# VESC_POWER_SCH.net
KiCad netlist of a schematic drawn in Altium Designer
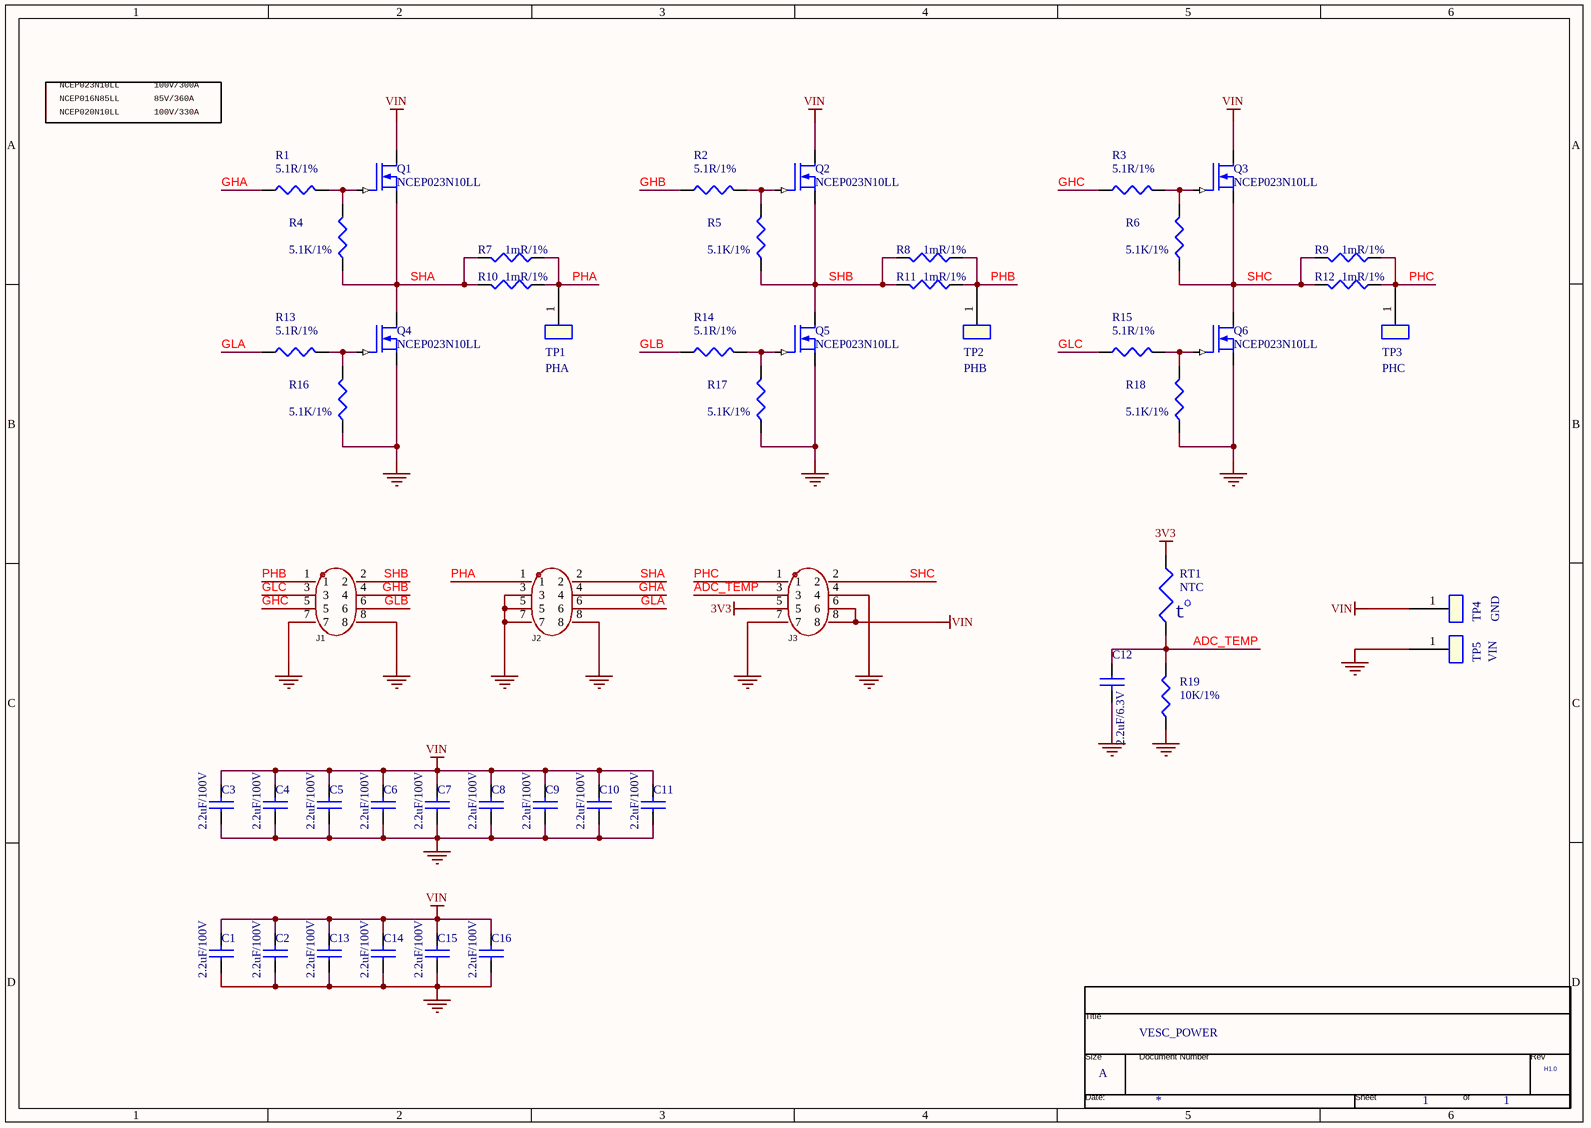
[diagram p0: VESC_POWER_SCH.SchDoc]

(export (version "E")
  (design (tool "Eeschema 10.0.6"))
  (components
    (comp (ref "*")
      (value "TitleBlock0")
      (fields
        (field (name "REVCODE") "H1.0")
        (field (name "TITLE") "VESC_POWER")
        (field (name "PAGE SIZE") "A")
        (field (name "PAGE NUMBER") "1")
        (field (name "PAGE COUNT") "1")
      )
      (libsource (lib "*") (part "TitleBlock0"))
    )
    (comp (ref "C1") (value "2.2uF/100V") (footprint "CAPC3225X230N") (libsource (lib "*") (part "CAP NP")))
    (comp (ref "C2") (value "2.2uF/100V") (footprint "CAPC3225X230N") (libsource (lib "*") (part "CAP NP")))
    (comp (ref "C3") (value "2.2uF/100V") (footprint "CAPC3225X230N") (libsource (lib "*") (part "CAP NP")))
    (comp (ref "C4") (value "2.2uF/100V") (footprint "CAPC3225X230N") (libsource (lib "*") (part "CAP NP")))
    (comp (ref "C5") (value "2.2uF/100V") (footprint "CAPC3225X230N") (libsource (lib "*") (part "CAP NP")))
    (comp (ref "C6") (value "2.2uF/100V") (footprint "CAPC3225X230N") (libsource (lib "*") (part "CAP NP")))
    (comp (ref "C7") (value "2.2uF/100V") (footprint "CAPC3225X230N") (libsource (lib "*") (part "CAP NP")))
    (comp (ref "C8") (value "2.2uF/100V") (footprint "CAPC3225X230N") (libsource (lib "*") (part "CAP NP")))
    (comp (ref "C9") (value "2.2uF/100V") (footprint "CAPC3225X230N") (libsource (lib "*") (part "CAP NP")))
    (comp (ref "C10") (value "2.2uF/100V") (footprint "CAPC3225X230N") (libsource (lib "*") (part "CAP NP")))
    (comp (ref "C11") (value "2.2uF/100V") (footprint "CAPC3225X230N") (libsource (lib "*") (part "CAP NP")))
    (comp (ref "C12") (value "2.2uF/6.3V") (footprint "C0603") (libsource (lib "*") (part "CAP NP")))
    (comp (ref "C13") (value "2.2uF/100V") (footprint "CAPC3225X230N") (libsource (lib "*") (part "CAP NP")))
    (comp (ref "C14") (value "2.2uF/100V") (footprint "CAPC3225X230N") (libsource (lib "*") (part "CAP NP")))
    (comp (ref "C15") (value "2.2uF/100V") (footprint "CAPC3225X230N") (libsource (lib "*") (part "CAP NP")))
    (comp (ref "C16") (value "2.2uF/100V") (footprint "CAPC3225X230N") (libsource (lib "*") (part "CAP NP")))
    (comp (ref "J1")
      (value "X6521WVS-2x04H-C60D74")
      (footprint "HDR-SMD_8P-P1.27-V-M-C2-C4-LS5.3")
      (fields (field (name "MANUFACTURER") "XKB Connection(中国星坤)"))
      (libsource (lib "VESC_POWER_Library") (part "X6521WVS-2x04H-C60D74"))
    )
    (comp (ref "J2")
      (value "X6521WVS-2x04H-C60D74")
      (footprint "HDR-SMD_8P-P1.27-V-M-C2-C4-LS5.3")
      (fields (field (name "MANUFACTURER") "XKB Connection(中国星坤)"))
      (libsource (lib "VESC_POWER_Library") (part "X6521WVS-2x04H-C60D74"))
    )
    (comp (ref "J3")
      (value "X6521WVS-2x04H-C60D74")
      (footprint "HDR-SMD_8P-P1.27-V-M-C2-C4-LS5.3")
      (fields (field (name "MANUFACTURER") "XKB Connection(中国星坤)"))
      (libsource (lib "VESC_POWER_Library") (part "X6521WVS-2x04H-C60D74"))
    )
    (comp (ref "Q1") (value "NCEP023N10LL") (footprint "TOLL") (libsource (lib "*") (part "MOSFET N")))
    (comp (ref "Q2") (value "NCEP023N10LL") (footprint "TOLL") (libsource (lib "*") (part "MOSFET N")))
    (comp (ref "Q3") (value "NCEP023N10LL") (footprint "TOLL") (libsource (lib "*") (part "MOSFET N")))
    (comp (ref "Q4") (value "NCEP023N10LL") (footprint "TOLL") (libsource (lib "*") (part "MOSFET N")))
    (comp (ref "Q5") (value "NCEP023N10LL") (footprint "TOLL") (libsource (lib "*") (part "MOSFET N")))
    (comp (ref "Q6") (value "NCEP023N10LL") (footprint "TOLL") (libsource (lib "*") (part "MOSFET N")))
    (comp (ref "R1") (value "5.1R/1%") (footprint "R0603") (libsource (lib "*") (part "RESISTOR")))
    (comp (ref "R2") (value "5.1R/1%") (footprint "R0603") (libsource (lib "*") (part "RESISTOR")))
    (comp (ref "R3") (value "5.1R/1%") (footprint "R0603") (libsource (lib "*") (part "RESISTOR")))
    (comp (ref "R4") (value "5.1K/1%") (footprint "R0603") (libsource (lib "*") (part "RESISTOR")))
    (comp (ref "R5") (value "5.1K/1%") (footprint "R0603") (libsource (lib "*") (part "RESISTOR")))
    (comp (ref "R6") (value "5.1K/1%") (footprint "R0603") (libsource (lib "*") (part "RESISTOR")))
    (comp (ref "R7") (value "1mR/1%") (footprint "R3920") (libsource (lib "*") (part "RESISTOR")))
    (comp (ref "R8") (value "1mR/1%") (footprint "R3920") (libsource (lib "*") (part "RESISTOR")))
    (comp (ref "R9") (value "1mR/1%") (footprint "R3920") (libsource (lib "*") (part "RESISTOR")))
    (comp (ref "R10") (value "1mR/1%") (footprint "R3920") (libsource (lib "*") (part "RESISTOR")))
    (comp (ref "R11") (value "1mR/1%") (footprint "R3920") (libsource (lib "*") (part "RESISTOR")))
    (comp (ref "R12") (value "1mR/1%") (footprint "R3920") (libsource (lib "*") (part "RESISTOR")))
    (comp (ref "R13") (value "5.1R/1%") (footprint "R0603") (libsource (lib "*") (part "RESISTOR")))
    (comp (ref "R14") (value "5.1R/1%") (footprint "R0603") (libsource (lib "*") (part "RESISTOR")))
    (comp (ref "R15") (value "5.1R/1%") (footprint "R0603") (libsource (lib "*") (part "RESISTOR")))
    (comp (ref "R16") (value "5.1K/1%") (footprint "R0603") (libsource (lib "*") (part "RESISTOR")))
    (comp (ref "R17") (value "5.1K/1%") (footprint "R0603") (libsource (lib "*") (part "RESISTOR")))
    (comp (ref "R18") (value "5.1K/1%") (footprint "R0603") (libsource (lib "*") (part "RESISTOR")))
    (comp (ref "R19") (value "10K/1%") (footprint "R0603") (libsource (lib "*") (part "RESISTOR")))
    (comp (ref "RT1") (value "NTC") (footprint "R0603") (libsource (lib "*") (part "NTC")))
    (comp (ref "TP1") (value "PHA") (footprint "TP_8x8") (libsource (lib "*") (part "TEST POINT")))
    (comp (ref "TP2") (value "PHB") (footprint "TP_8x8") (libsource (lib "*") (part "TEST POINT")))
    (comp (ref "TP3") (value "PHC") (footprint "TP_8x8") (libsource (lib "*") (part "TEST POINT")))
    (comp (ref "TP4") (value "GND") (footprint "TP_8x8") (libsource (lib "") (part "TEST POINT_1")))
    (comp (ref "TP5") (value "VIN") (footprint "TP_8x8") (libsource (lib "") (part "TEST POINT_1")))
  )
  (nets
    (net (code "1") (name "/ADC_TEMP") (class "Default")
      (node (ref "C12") (pin "1") (pinfunction "1_1") (pintype "passive"))
      (node (ref "J3") (pin "3") (pinfunction "3_3") (pintype "passive"))
      (node (ref "R19") (pin "2") (pinfunction "2_2") (pintype "passive"))
      (node (ref "RT1") (pin "2") (pinfunction "2_2") (pintype "passive"))
    )
    (net (code "2") (name "/GHA") (class "Default")
      (node (ref "J2") (pin "4") (pinfunction "4_4") (pintype "passive"))
      (node (ref "R1") (pin "1") (pinfunction "1_1") (pintype "passive"))
    )
    (net (code "3") (name "/GHB") (class "Default")
      (node (ref "J1") (pin "4") (pinfunction "4_4") (pintype "passive"))
      (node (ref "R2") (pin "1") (pinfunction "1_1") (pintype "passive"))
    )
    (net (code "4") (name "/GHC") (class "Default")
      (node (ref "J1") (pin "5") (pinfunction "5_5") (pintype "passive"))
      (node (ref "R3") (pin "1") (pinfunction "1_1") (pintype "passive"))
    )
    (net (code "5") (name "/GLA") (class "Default")
      (node (ref "J2") (pin "6") (pinfunction "6_6") (pintype "passive"))
      (node (ref "R13") (pin "1") (pinfunction "1_1") (pintype "passive"))
    )
    (net (code "6") (name "/GLB") (class "Default")
      (node (ref "J1") (pin "6") (pinfunction "6_6") (pintype "passive"))
      (node (ref "R14") (pin "1") (pinfunction "1_1") (pintype "passive"))
    )
    (net (code "7") (name "/GLC") (class "Default")
      (node (ref "J1") (pin "3") (pinfunction "3_3") (pintype "passive"))
      (node (ref "R15") (pin "1") (pinfunction "1_1") (pintype "passive"))
    )
    (net (code "8") (name "/PHA") (class "Default")
      (node (ref "J2") (pin "1") (pinfunction "1_1") (pintype "passive"))
      (node (ref "R10") (pin "1") (pinfunction "1_1") (pintype "passive"))
      (node (ref "R7") (pin "1") (pinfunction "1_1") (pintype "passive"))
      (node (ref "TP1") (pin "1") (pinfunction "1_1") (pintype "passive"))
    )
    (net (code "9") (name "/PHB") (class "Default")
      (node (ref "J1") (pin "1") (pinfunction "1_1") (pintype "passive"))
      (node (ref "R11") (pin "1") (pinfunction "1_1") (pintype "passive"))
      (node (ref "R8") (pin "1") (pinfunction "1_1") (pintype "passive"))
      (node (ref "TP2") (pin "1") (pinfunction "1_1") (pintype "passive"))
    )
    (net (code "10") (name "/PHC") (class "Default")
      (node (ref "J3") (pin "1") (pinfunction "1_1") (pintype "passive"))
      (node (ref "R12") (pin "1") (pinfunction "1_1") (pintype "passive"))
      (node (ref "R9") (pin "1") (pinfunction "1_1") (pintype "passive"))
      (node (ref "TP3") (pin "1") (pinfunction "1_1") (pintype "passive"))
    )
    (net (code "11") (name "/SHA") (class "Default")
      (node (ref "J2") (pin "2") (pinfunction "2_2") (pintype "passive"))
      (node (ref "Q1") (pin "3") (pinfunction "SOURCE_3") (pintype "passive"))
      (node (ref "Q4") (pin "2") (pinfunction "DRAIN_2") (pintype "passive"))
      (node (ref "R10") (pin "2") (pinfunction "2_2") (pintype "passive"))
      (node (ref "R4") (pin "1") (pinfunction "1_1") (pintype "passive"))
      (node (ref "R7") (pin "2") (pinfunction "2_2") (pintype "passive"))
    )
    (net (code "12") (name "/SHB") (class "Default")
      (node (ref "J1") (pin "2") (pinfunction "2_2") (pintype "passive"))
      (node (ref "Q2") (pin "3") (pinfunction "SOURCE_3") (pintype "passive"))
      (node (ref "Q5") (pin "2") (pinfunction "DRAIN_2") (pintype "passive"))
      (node (ref "R11") (pin "2") (pinfunction "2_2") (pintype "passive"))
      (node (ref "R5") (pin "1") (pinfunction "1_1") (pintype "passive"))
      (node (ref "R8") (pin "2") (pinfunction "2_2") (pintype "passive"))
    )
    (net (code "13") (name "/SHC") (class "Default")
      (node (ref "J3") (pin "2") (pinfunction "2_2") (pintype "passive"))
      (node (ref "Q3") (pin "3") (pinfunction "SOURCE_3") (pintype "passive"))
      (node (ref "Q6") (pin "2") (pinfunction "DRAIN_2") (pintype "passive"))
      (node (ref "R12") (pin "2") (pinfunction "2_2") (pintype "passive"))
      (node (ref "R6") (pin "1") (pinfunction "1_1") (pintype "passive"))
      (node (ref "R9") (pin "2") (pinfunction "2_2") (pintype "passive"))
    )
    (net (code "14") (name "3V3") (class "Default")
      (node (ref "J3") (pin "5") (pinfunction "5_5") (pintype "passive"))
      (node (ref "RT1") (pin "1") (pinfunction "1_1") (pintype "passive"))
    )
    (net (code "15") (name "GND") (class "Default")
      (node (ref "C1") (pin "1") (pinfunction "1_1") (pintype "passive"))
      (node (ref "C10") (pin "1") (pinfunction "1_1") (pintype "passive"))
      (node (ref "C11") (pin "1") (pinfunction "1_1") (pintype "passive"))
      (node (ref "C12") (pin "2") (pinfunction "2_2") (pintype "passive"))
      (node (ref "C13") (pin "1") (pinfunction "1_1") (pintype "passive"))
      (node (ref "C14") (pin "1") (pinfunction "1_1") (pintype "passive"))
      (node (ref "C15") (pin "1") (pinfunction "1_1") (pintype "passive"))
      (node (ref "C16") (pin "1") (pinfunction "1_1") (pintype "passive"))
      (node (ref "C2") (pin "1") (pinfunction "1_1") (pintype "passive"))
      (node (ref "C3") (pin "1") (pinfunction "1_1") (pintype "passive"))
      (node (ref "C4") (pin "1") (pinfunction "1_1") (pintype "passive"))
      (node (ref "C5") (pin "1") (pinfunction "1_1") (pintype "passive"))
      (node (ref "C6") (pin "1") (pinfunction "1_1") (pintype "passive"))
      (node (ref "C7") (pin "1") (pinfunction "1_1") (pintype "passive"))
      (node (ref "C8") (pin "1") (pinfunction "1_1") (pintype "passive"))
      (node (ref "C9") (pin "1") (pinfunction "1_1") (pintype "passive"))
      (node (ref "J1") (pin "7") (pinfunction "7_7") (pintype "passive"))
      (node (ref "J1") (pin "8") (pinfunction "8_8") (pintype "passive"))
      (node (ref "J2") (pin "3") (pinfunction "3_3") (pintype "passive"))
      (node (ref "J2") (pin "5") (pinfunction "5_5") (pintype "passive"))
      (node (ref "J2") (pin "7") (pinfunction "7_7") (pintype "passive"))
      (node (ref "J2") (pin "8") (pinfunction "8_8") (pintype "passive"))
      (node (ref "J3") (pin "4") (pinfunction "4_4") (pintype "passive"))
      (node (ref "J3") (pin "7") (pinfunction "7_7") (pintype "passive"))
      (node (ref "Q4") (pin "3") (pinfunction "SOURCE_3") (pintype "passive"))
      (node (ref "Q5") (pin "3") (pinfunction "SOURCE_3") (pintype "passive"))
      (node (ref "Q6") (pin "3") (pinfunction "SOURCE_3") (pintype "passive"))
      (node (ref "R16") (pin "1") (pinfunction "1_1") (pintype "passive"))
      (node (ref "R17") (pin "1") (pinfunction "1_1") (pintype "passive"))
      (node (ref "R18") (pin "1") (pinfunction "1_1") (pintype "passive"))
      (node (ref "R19") (pin "1") (pinfunction "1_1") (pintype "passive"))
      (node (ref "TP5") (pin "1") (pinfunction "1_1") (pintype "passive"))
    )
    (net (code "16") (name "Net-(Q1-GATE)") (class "Default")
      (node (ref "Q1") (pin "1") (pinfunction "GATE_1") (pintype "input"))
      (node (ref "R1") (pin "2") (pinfunction "2_2") (pintype "passive"))
      (node (ref "R4") (pin "2") (pinfunction "2_2") (pintype "passive"))
    )
    (net (code "17") (name "Net-(Q2-GATE)") (class "Default")
      (node (ref "Q2") (pin "1") (pinfunction "GATE_1") (pintype "input"))
      (node (ref "R2") (pin "2") (pinfunction "2_2") (pintype "passive"))
      (node (ref "R5") (pin "2") (pinfunction "2_2") (pintype "passive"))
    )
    (net (code "18") (name "Net-(Q3-GATE)") (class "Default")
      (node (ref "Q3") (pin "1") (pinfunction "GATE_1") (pintype "input"))
      (node (ref "R3") (pin "2") (pinfunction "2_2") (pintype "passive"))
      (node (ref "R6") (pin "2") (pinfunction "2_2") (pintype "passive"))
    )
    (net (code "19") (name "Net-(Q4-GATE)") (class "Default")
      (node (ref "Q4") (pin "1") (pinfunction "GATE_1") (pintype "input"))
      (node (ref "R13") (pin "2") (pinfunction "2_2") (pintype "passive"))
      (node (ref "R16") (pin "2") (pinfunction "2_2") (pintype "passive"))
    )
    (net (code "20") (name "Net-(Q5-GATE)") (class "Default")
      (node (ref "Q5") (pin "1") (pinfunction "GATE_1") (pintype "input"))
      (node (ref "R14") (pin "2") (pinfunction "2_2") (pintype "passive"))
      (node (ref "R17") (pin "2") (pinfunction "2_2") (pintype "passive"))
    )
    (net (code "21") (name "Net-(Q6-GATE)") (class "Default")
      (node (ref "Q6") (pin "1") (pinfunction "GATE_1") (pintype "input"))
      (node (ref "R15") (pin "2") (pinfunction "2_2") (pintype "passive"))
      (node (ref "R18") (pin "2") (pinfunction "2_2") (pintype "passive"))
    )
    (net (code "22") (name "VIN") (class "Default")
      (node (ref "C1") (pin "2") (pinfunction "2_2") (pintype "passive"))
      (node (ref "C10") (pin "2") (pinfunction "2_2") (pintype "passive"))
      (node (ref "C11") (pin "2") (pinfunction "2_2") (pintype "passive"))
      (node (ref "C13") (pin "2") (pinfunction "2_2") (pintype "passive"))
      (node (ref "C14") (pin "2") (pinfunction "2_2") (pintype "passive"))
      (node (ref "C15") (pin "2") (pinfunction "2_2") (pintype "passive"))
      (node (ref "C16") (pin "2") (pinfunction "2_2") (pintype "passive"))
      (node (ref "C2") (pin "2") (pinfunction "2_2") (pintype "passive"))
      (node (ref "C3") (pin "2") (pinfunction "2_2") (pintype "passive"))
      (node (ref "C4") (pin "2") (pinfunction "2_2") (pintype "passive"))
      (node (ref "C5") (pin "2") (pinfunction "2_2") (pintype "passive"))
      (node (ref "C6") (pin "2") (pinfunction "2_2") (pintype "passive"))
      (node (ref "C7") (pin "2") (pinfunction "2_2") (pintype "passive"))
      (node (ref "C8") (pin "2") (pinfunction "2_2") (pintype "passive"))
      (node (ref "C9") (pin "2") (pinfunction "2_2") (pintype "passive"))
      (node (ref "J3") (pin "6") (pinfunction "6_6") (pintype "passive"))
      (node (ref "J3") (pin "8") (pinfunction "8_8") (pintype "passive"))
      (node (ref "Q1") (pin "2") (pinfunction "DRAIN_2") (pintype "passive"))
      (node (ref "Q2") (pin "2") (pinfunction "DRAIN_2") (pintype "passive"))
      (node (ref "Q3") (pin "2") (pinfunction "DRAIN_2") (pintype "passive"))
      (node (ref "TP4") (pin "1") (pinfunction "1_1") (pintype "passive"))
    )
  )
)
